# mcu.net
KiCad netlist of a schematic drawn in Altium Designer
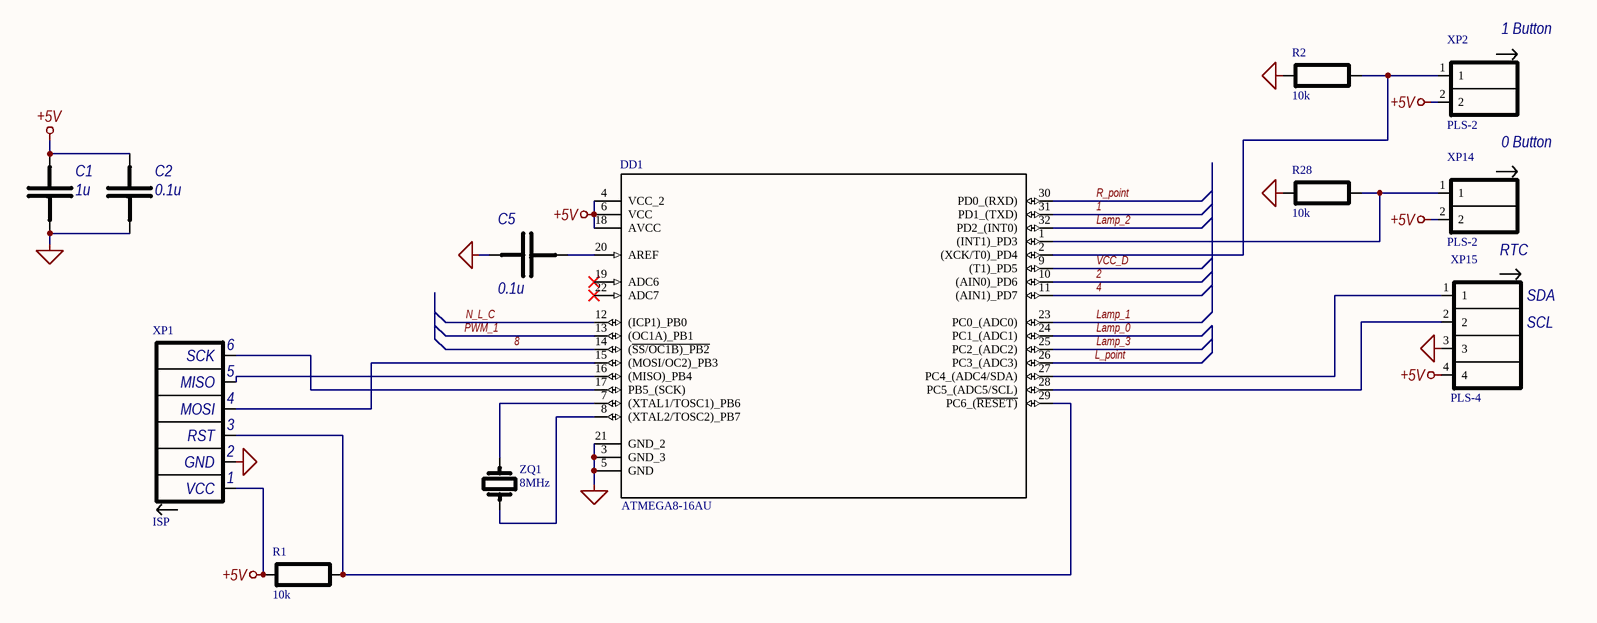
[diagram p0: mcu.SchDoc]

(export (version "E")
  (design (tool "Eeschema 10.0.6"))
  (components
    (comp (ref "C1")
      (value "1u")
      (footprint "CR2012-0805")
      (libsource (lib "sobol_lib") (part "C0805-1u-X7R"))
    )
    (comp (ref "C2")
      (value "0.1u")
      (footprint "CR2012-0805")
      (libsource (lib "sobol_lib") (part "C0805-0.1u-X7R"))
    )
    (comp (ref "C5")
      (value "0.1u")
      (footprint "CR2012-0805")
      (libsource (lib "sobol_lib") (part "C0805-0.1u-X7R"))
    )
    (comp (ref "DD1")
      (value "ATMEGA8-16AU")
      (footprint "*QFP80P900X900X120-32N")
      (description "AVR AVRВ® ATmega Microcontroller IC 8-Bit 16MHz 8KB _4K x 16_ FLASH 32-TQFP _7x7_")
      (fields (field (name "MF") "Microchip Technology"))
      (libsource (lib "sobol_lib") (part "ATMEGA8-16AU"))
    )
    (comp (ref "R1")
      (value "10k")
      (footprint "CR2012-0805")
      (libsource (lib "sobol_lib") (part "R0805-10k-5%"))
    )
    (comp (ref "R2")
      (value "10k")
      (footprint "CR2012-0805")
      (libsource (lib "sobol_lib") (part "R0805-10k-5%"))
    )
    (comp (ref "R28")
      (value "10k")
      (footprint "CR2012-0805")
      (libsource (lib "sobol_lib") (part "R0805-10k-5%"))
    )
    (comp (ref "XP1") (value "ISP") (footprint "PLS-6") (libsource (lib "sobol_lib") (part "ISP")))
    (comp (ref "XP2") (value "PLS-2") (footprint "PLS-2") (libsource (lib "sobol_lib") (part "PLS-2")))
    (comp (ref "XP14") (value "PLS-2") (footprint "PLS-2") (libsource (lib "sobol_lib") (part "PLS-2")))
    (comp (ref "XP15") (value "PLS-4") (footprint "PLS-4") (libsource (lib "sobol_lib") (part "PLS-4")))
    (comp (ref "ZQ1")
      (value "8MHz")
      (footprint "CRYSTAL")
      (libsource (lib "sobol_lib") (part "Crystal_8MHz"))
    )
  )
  (nets
    (net (code "1") (name "+5V") (class "Default")
      (node (ref "C1") (pin "1") (pinfunction "1_1") (pintype "passive"))
      (node (ref "C2") (pin "1") (pinfunction "1_1") (pintype "passive"))
      (node (ref "DD1") (pin "18") (pinfunction "AVCC_18") (pintype "power_in"))
      (node (ref "DD1") (pin "4") (pinfunction "VCC_2_4") (pintype "power_in"))
      (node (ref "DD1") (pin "6") (pinfunction "VCC_6") (pintype "power_in"))
      (node (ref "R1") (pin "1") (pinfunction "1_1") (pintype "passive"))
      (node (ref "XP1") (pin "1") (pinfunction "VCC_1") (pintype "passive"))
      (node (ref "XP14") (pin "2") (pinfunction "2_2") (pintype "passive"))
      (node (ref "XP15") (pin "4") (pinfunction "4_4") (pintype "passive"))
      (node (ref "XP2") (pin "2") (pinfunction "2_2") (pintype "passive"))
    )
    (net (code "2") (name "/1") (class "Default")
      (node (ref "DD1") (pin "31") (pinfunction "PD1_(TXD)_31") (pintype "bidirectional"))
    )
    (net (code "3") (name "/2") (class "Default")
      (node (ref "DD1") (pin "10") (pinfunction "(AIN0)_PD6_10") (pintype "bidirectional"))
    )
    (net (code "4") (name "/4") (class "Default")
      (node (ref "DD1") (pin "11") (pinfunction "(AIN1)_PD7_11") (pintype "bidirectional"))
    )
    (net (code "5") (name "/8") (class "Default")
      (node (ref "DD1") (pin "14") (pinfunction "(~{SS/OC1B)_PB2}_14") (pintype "bidirectional"))
    )
    (net (code "6") (name "/L_point") (class "Default")
      (node (ref "DD1") (pin "26") (pinfunction "PC3_(ADC3)_26") (pintype "bidirectional"))
    )
    (net (code "7") (name "/Lamp_0") (class "Default")
      (node (ref "DD1") (pin "24") (pinfunction "PC1_(ADC1)_24") (pintype "bidirectional"))
    )
    (net (code "8") (name "/Lamp_1") (class "Default")
      (node (ref "DD1") (pin "23") (pinfunction "PC0_(ADC0)_23") (pintype "bidirectional"))
    )
    (net (code "9") (name "/Lamp_2") (class "Default")
      (node (ref "DD1") (pin "32") (pinfunction "PD2_(INT0)_32") (pintype "bidirectional"))
    )
    (net (code "10") (name "/Lamp_3") (class "Default")
      (node (ref "DD1") (pin "25") (pinfunction "PC2_(ADC2)_25") (pintype "bidirectional"))
    )
    (net (code "11") (name "/N_L_C") (class "Default")
      (node (ref "DD1") (pin "12") (pinfunction "(ICP1)_PB0_12") (pintype "bidirectional"))
    )
    (net (code "12") (name "/PWM_1") (class "Default")
      (node (ref "DD1") (pin "13") (pinfunction "(OC1A)_PB1_13") (pintype "bidirectional"))
    )
    (net (code "13") (name "/R_point") (class "Default")
      (node (ref "DD1") (pin "30") (pinfunction "PD0_(RXD)_30") (pintype "bidirectional"))
    )
    (net (code "14") (name "/VCC_D") (class "Default")
      (node (ref "DD1") (pin "9") (pinfunction "(T1)_PD5_9") (pintype "bidirectional"))
    )
    (net (code "15") (name "Net-(DD1-(INT1)_PD3)") (class "Default")
      (node (ref "DD1") (pin "1") (pinfunction "(INT1)_PD3_1") (pintype "bidirectional"))
      (node (ref "R28") (pin "2") (pinfunction "2_2") (pintype "passive"))
      (node (ref "XP14") (pin "1") (pinfunction "1_1") (pintype "passive"))
    )
    (net (code "16") (name "Net-(DD1-(MISO)_PB4)") (class "Default")
      (node (ref "DD1") (pin "16") (pinfunction "(MISO)_PB4_16") (pintype "bidirectional"))
      (node (ref "XP1") (pin "5") (pinfunction "MISO_5") (pintype "passive"))
    )
    (net (code "17") (name "Net-(DD1-(MOSI{slash}OC2)_PB3)") (class "Default")
      (node (ref "DD1") (pin "15") (pinfunction "(MOSI/OC2)_PB3_15") (pintype "bidirectional"))
      (node (ref "XP1") (pin "4") (pinfunction "MOSI_4") (pintype "passive"))
    )
    (net (code "18") (name "Net-(DD1-(XCK{slash}T0)_PD4)") (class "Default")
      (node (ref "DD1") (pin "2") (pinfunction "(XCK/T0)_PD4_2") (pintype "bidirectional"))
      (node (ref "R2") (pin "2") (pinfunction "2_2") (pintype "passive"))
      (node (ref "XP2") (pin "1") (pinfunction "1_1") (pintype "passive"))
    )
    (net (code "19") (name "Net-(DD1-(XTAL1{slash}TOSC1)_PB6)") (class "Default")
      (node (ref "DD1") (pin "7") (pinfunction "(XTAL1/TOSC1)_PB6_7") (pintype "bidirectional"))
      (node (ref "ZQ1") (pin "1") (pinfunction "1_1") (pintype "passive"))
    )
    (net (code "20") (name "Net-(DD1-(XTAL2{slash}TOSC2)_PB7)") (class "Default")
      (node (ref "DD1") (pin "8") (pinfunction "(XTAL2/TOSC2)_PB7_8") (pintype "bidirectional"))
      (node (ref "ZQ1") (pin "2") (pinfunction "2_2") (pintype "passive"))
    )
    (net (code "21") (name "Net-(DD1-AREF)") (class "Default")
      (node (ref "C5") (pin "2") (pinfunction "2_2") (pintype "passive"))
      (node (ref "DD1") (pin "20") (pinfunction "AREF_20") (pintype "input"))
    )
    (net (code "22") (name "Net-(DD1-PB5_(SCK))") (class "Default")
      (node (ref "DD1") (pin "17") (pinfunction "PB5_(SCK)_17") (pintype "bidirectional"))
      (node (ref "XP1") (pin "6") (pinfunction "SCK_6") (pintype "passive"))
    )
    (net (code "23") (name "Net-(DD1-PC4_(ADC4{slash}SDA))") (class "Default")
      (node (ref "DD1") (pin "27") (pinfunction "PC4_(ADC4/SDA)_27") (pintype "bidirectional"))
      (node (ref "XP15") (pin "1") (pinfunction "1_1") (pintype "passive"))
    )
    (net (code "24") (name "Net-(DD1-PC5_(ADC5{slash}SCL))") (class "Default")
      (node (ref "DD1") (pin "28") (pinfunction "PC5_(ADC5/SCL)_28") (pintype "bidirectional"))
      (node (ref "XP15") (pin "2") (pinfunction "2_2") (pintype "passive"))
    )
    (net (code "25") (name "Net-(DD1-PC6_(~{RESET)})") (class "Default")
      (node (ref "DD1") (pin "29") (pinfunction "PC6_(~{RESET)}_29") (pintype "bidirectional"))
      (node (ref "R1") (pin "2") (pinfunction "2_2") (pintype "passive"))
      (node (ref "XP1") (pin "3") (pinfunction "RST_3") (pintype "passive"))
    )
    (net (code "26") (name "SGND") (class "Default")
      (node (ref "C1") (pin "2") (pinfunction "2_2") (pintype "passive"))
      (node (ref "C2") (pin "2") (pinfunction "2_2") (pintype "passive"))
      (node (ref "C5") (pin "1") (pinfunction "1_1") (pintype "passive"))
      (node (ref "DD1") (pin "21") (pinfunction "GND_2_21") (pintype "passive"))
      (node (ref "DD1") (pin "3") (pinfunction "GND_3_3") (pintype "passive"))
      (node (ref "DD1") (pin "5") (pinfunction "GND_5") (pintype "passive"))
      (node (ref "R2") (pin "1") (pinfunction "1_1") (pintype "passive"))
      (node (ref "R28") (pin "1") (pinfunction "1_1") (pintype "passive"))
      (node (ref "XP1") (pin "2") (pinfunction "GND_2") (pintype "passive"))
      (node (ref "XP15") (pin "3") (pinfunction "3_3") (pintype "passive"))
    )
    (net (code "27") (name "unconnected-(DD1-ADC6-Pad19)") (class "Default")
      (node (ref "DD1") (pin "19") (pinfunction "ADC6_19") (pintype "input+no_connect"))
    )
    (net (code "28") (name "unconnected-(DD1-ADC7-Pad22)") (class "Default")
      (node (ref "DD1") (pin "22") (pinfunction "ADC7_22") (pintype "input+no_connect"))
    )
  )
)
